# main.net
KiCad netlist of a schematic drawn in Altium Designer
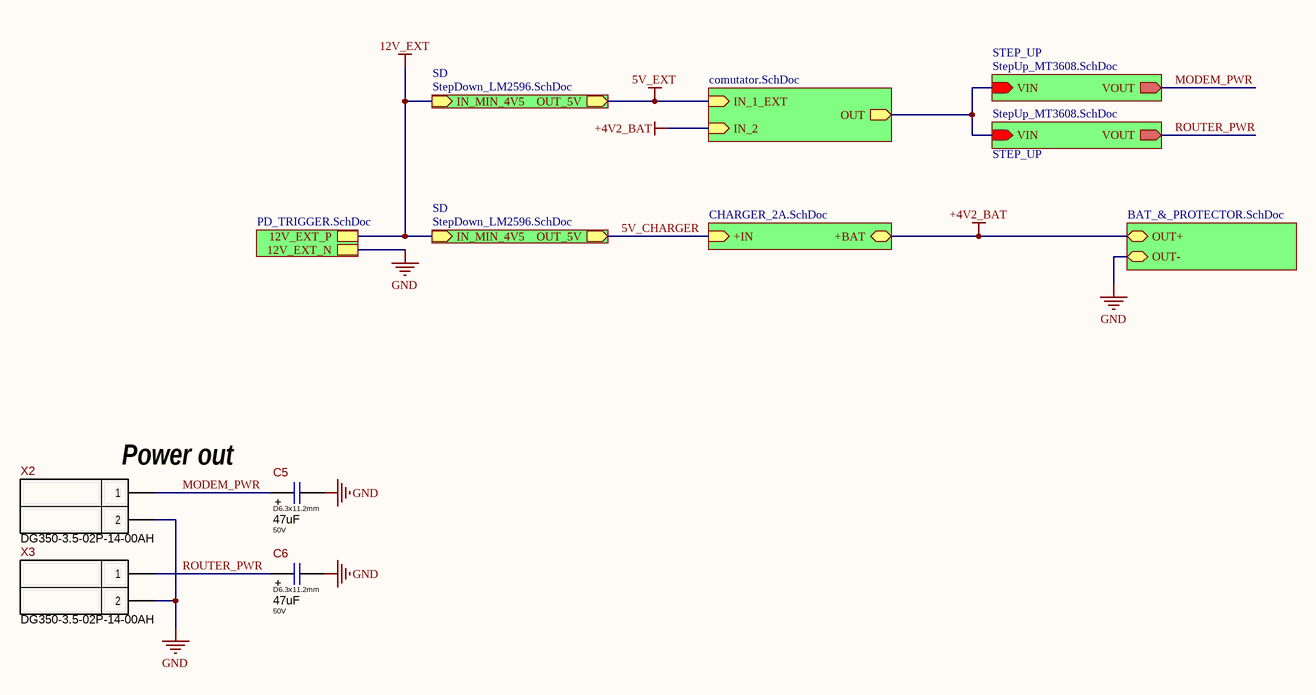
[diagram p0: main.SchDoc]

(export (version "E")
  (design (tool "Eeschema 10.0.6"))
  (components
    (comp (ref "C5")
      (value "47uF")
      (footprint "CAP-AE-PTH-63D05x112H15")
      (fields
        (field (name "PACKAGE") "D6.3x11.2mm")
        (field (name "VOLTAGE") "50V")
        (field (name "PART NUMBER") "EEU-FR1H470")
        (field (name "MANUFACTURER") "Panasonic")
        (field (name "TOLERANCE") "±20%")
      )
      (libsource (lib "capacitors") (part "EEU-FR1H470"))
    )
    (comp (ref "C6")
      (value "47uF")
      (footprint "CAP-AE-PTH-63D05x112H15")
      (fields
        (field (name "PACKAGE") "D6.3x11.2mm")
        (field (name "VOLTAGE") "50V")
        (field (name "PART NUMBER") "EEU-FR1H470")
        (field (name "MANUFACTURER") "Panasonic")
        (field (name "TOLERANCE") "±20%")
      )
      (libsource (lib "capacitors") (part "EEU-FR1H470"))
    )
    (comp (ref "X2")
      (value "DG350-3.5-02P")
      (footprint "DG350-3.5-02P-14-00AH")
      (description "Screw Terminal, 3.5mm Pitch, 2 pin, Green")
      (fields (field (name "PART NUMBER") "DG350-3.5-02P-14-00AH") (field (name "MANUFACTURER") "Degson"))
      (libsource (lib "connectors") (part "DG350-3.5-02P-14-00AH"))
    )
    (comp (ref "X3")
      (value "DG350-3.5-02P")
      (footprint "DG350-3.5-02P-14-00AH")
      (description "Screw Terminal, 3.5mm Pitch, 2 pin, Green")
      (fields (field (name "PART NUMBER") "DG350-3.5-02P-14-00AH") (field (name "MANUFACTURER") "Degson"))
      (libsource (lib "connectors") (part "DG350-3.5-02P-14-00AH"))
    )
  )
  (nets
    (net (code "3") (name "/MODEM_PWR") (class "Default")
      (node (ref "C5") (pin "1") (pinfunction "1_1") (pintype "passive"))
      (node (ref "X2") (pin "1") (pinfunction "1_1") (pintype "passive"))
    )
    (net (code "5") (name "/ROUTER_PWR") (class "Default")
      (node (ref "C6") (pin "1") (pinfunction "1_1") (pintype "passive"))
      (node (ref "X3") (pin "1") (pinfunction "1_1") (pintype "passive"))
    )
    (net (code "8") (name "GND") (class "Default")
      (node (ref "C5") (pin "2") (pinfunction "2_2") (pintype "passive"))
      (node (ref "C6") (pin "2") (pinfunction "2_2") (pintype "passive"))
      (node (ref "X2") (pin "2") (pinfunction "2_2") (pintype "passive"))
      (node (ref "X3") (pin "2") (pinfunction "2_2") (pintype "passive"))
    )
  )
)
